# Connector_0_V1_01.net
KiCad netlist of a schematic drawn in Altium Designer
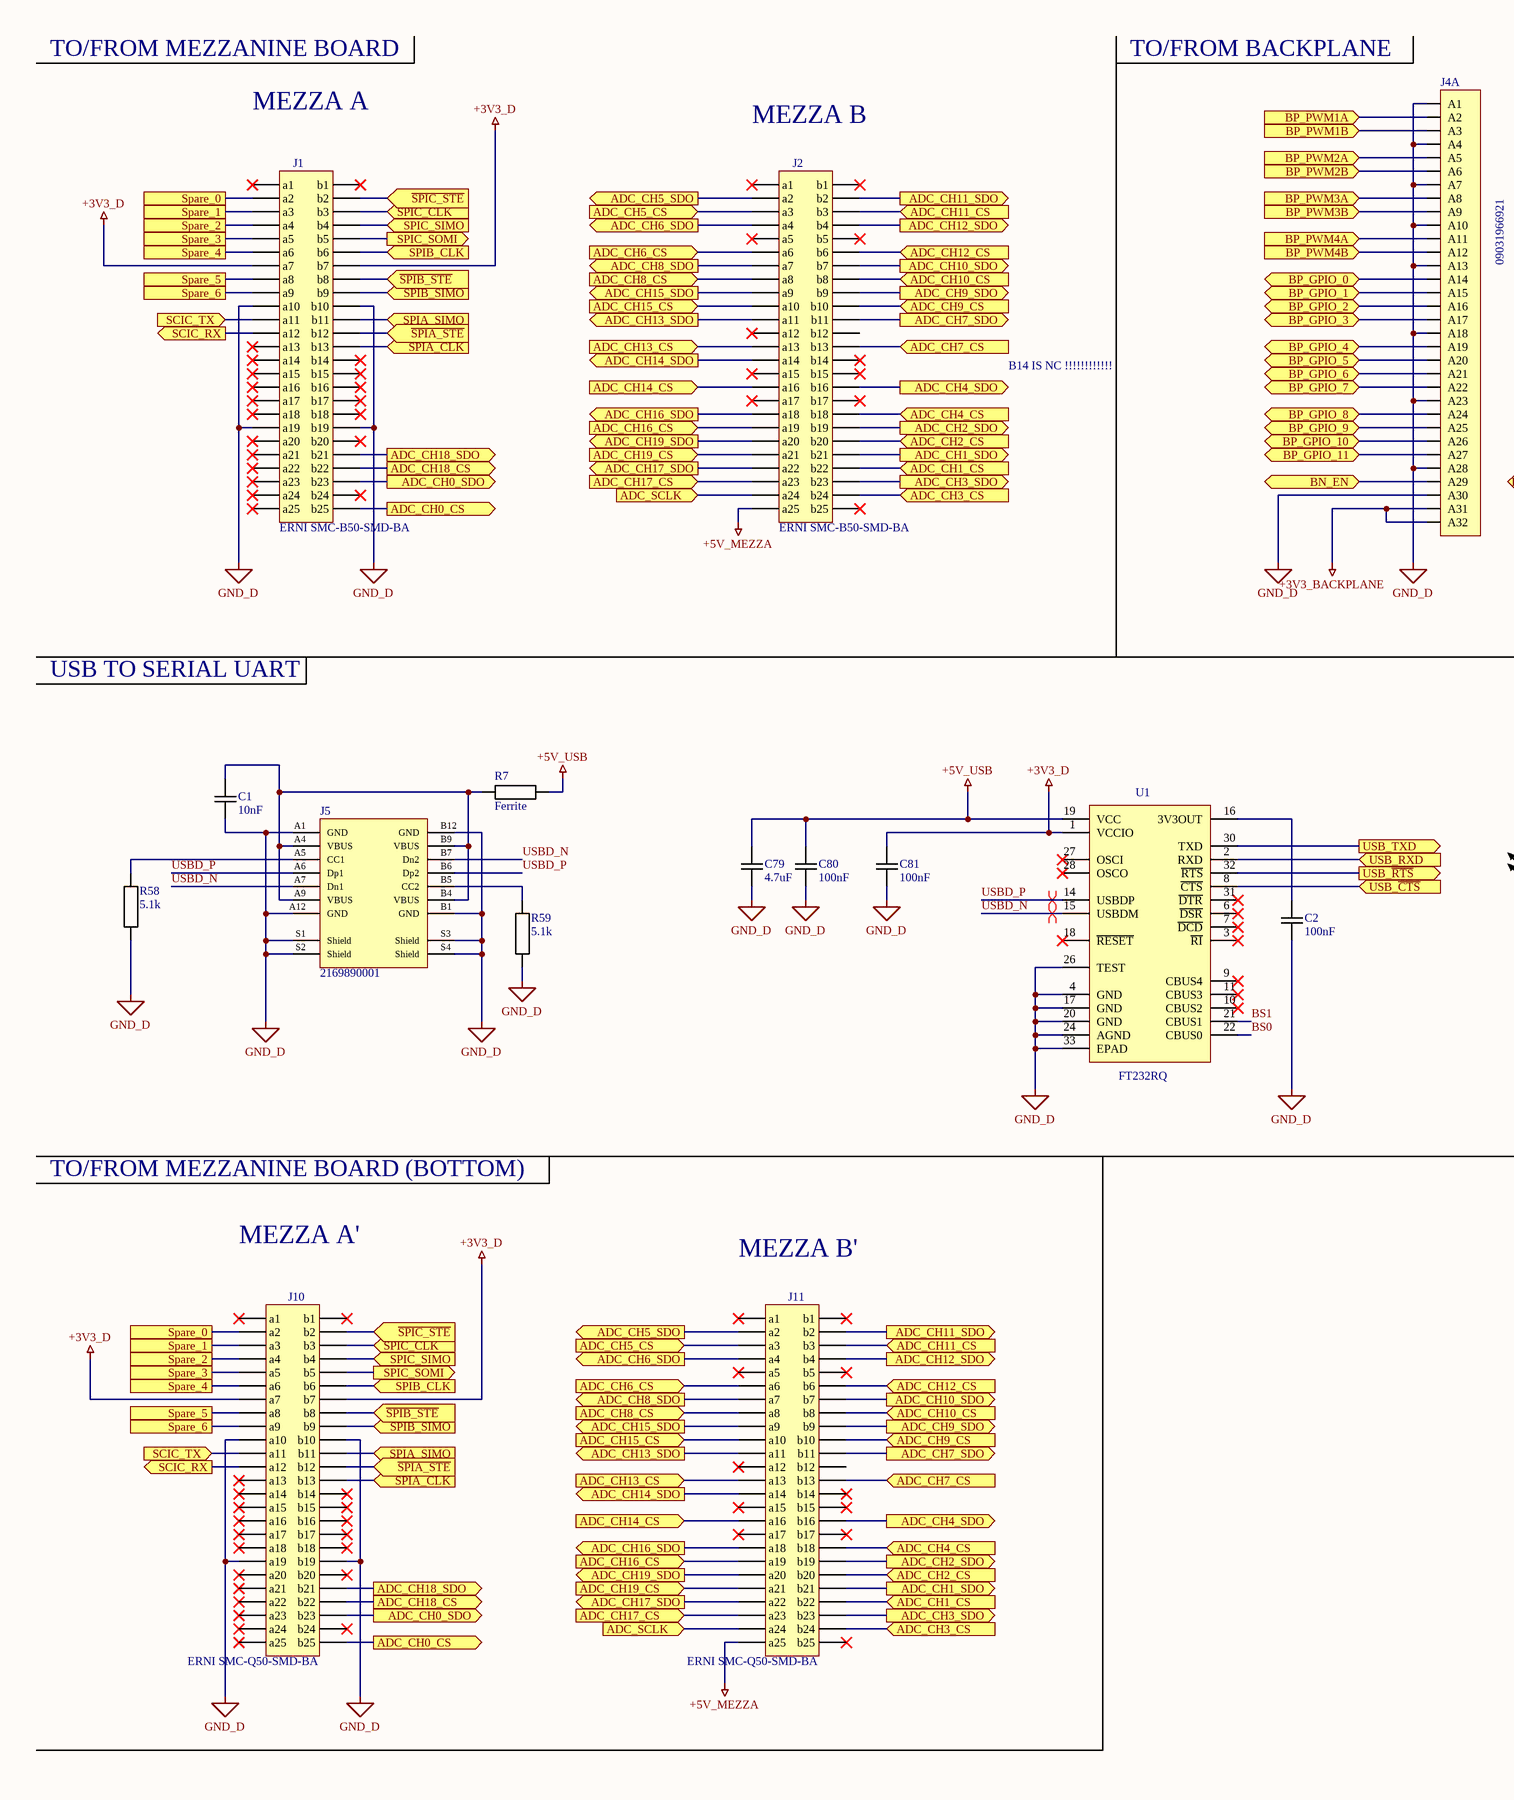
[diagram p0: Connector_0_V1_01.SchDoc, left]
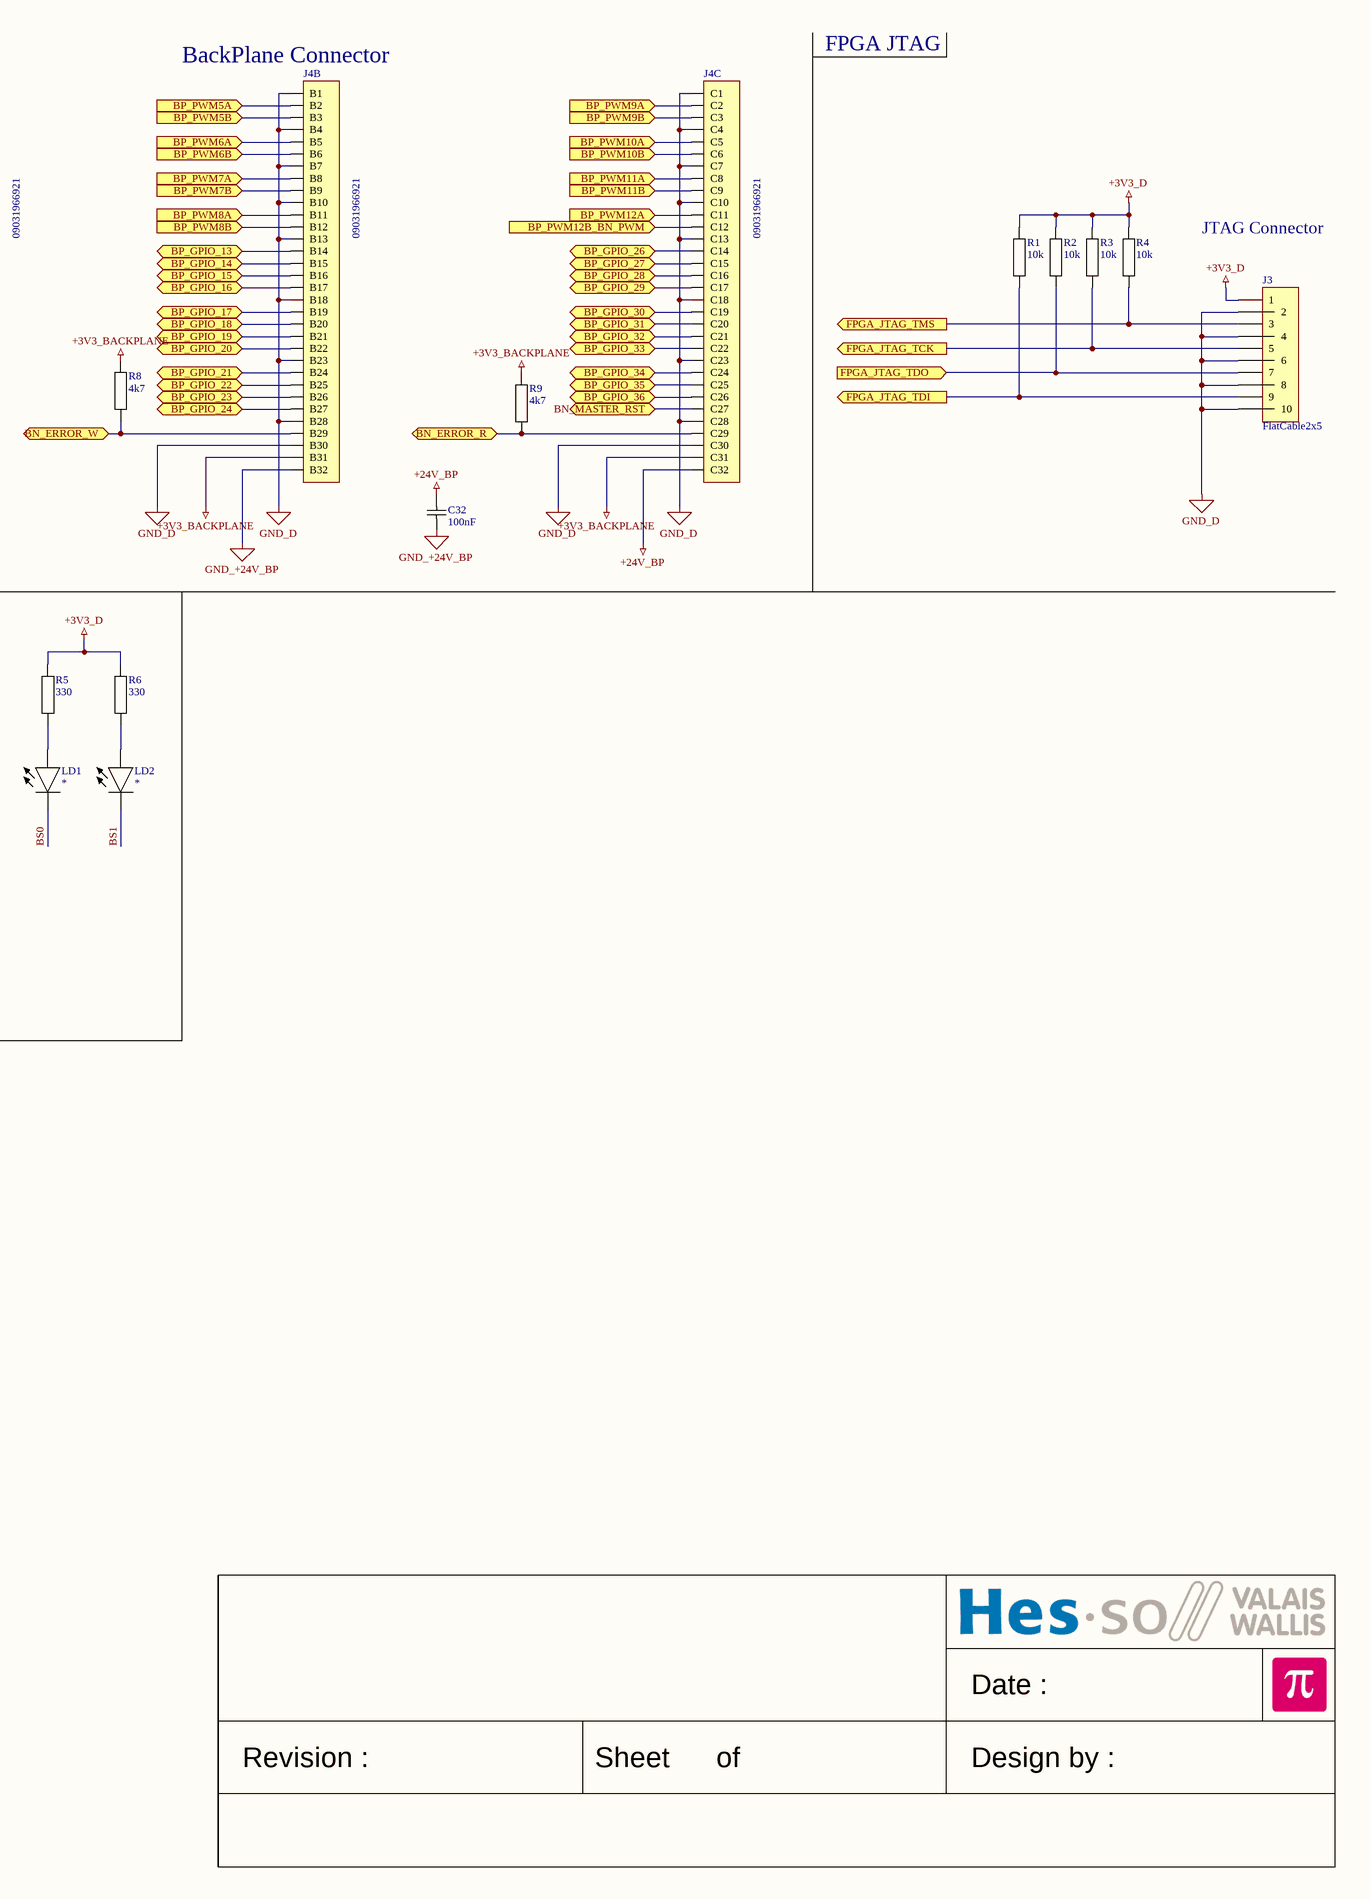
[diagram p1: Connector_0_V1_01.SchDoc, right]

(export (version "E")
  (design (tool "Eeschema 10.0.6"))
  (components
    (comp (ref "C1")
      (value "10nF")
      (footprint "CAPACITOR 1608 REFLOW")
      (description "Capacitor X7R 10% 50V 1608(0603)")
      (libsource (lib "Capacitor") (part "Capacitor"))
    )
    (comp (ref "C2")
      (value "100nF")
      (footprint "CAPACITOR 1608 REFLOW")
      (description "Capacitor X7R 10% 50V 1608(0603)")
      (libsource (lib "Capacitor") (part "Capacitor"))
    )
    (comp (ref "C32")
      (value "100nF")
      (footprint "CAPACITOR 1608 REFLOW")
      (description "Capacitor X7R 10% 50V 1608(0603)")
      (libsource (lib "Capacitor") (part "Capacitor"))
    )
    (comp (ref "C79")
      (value "4.7uF")
      (footprint "CAPACITOR 1608 REFLOW")
      (description "Capacitor X7R 10% 50V 1608(0603)")
      (libsource (lib "Capacitor") (part "Capacitor"))
    )
    (comp (ref "C80")
      (value "100nF")
      (footprint "CAPACITOR 1608 REFLOW")
      (description "Capacitor X7R 10% 50V 1608(0603)")
      (libsource (lib "Capacitor") (part "Capacitor"))
    )
    (comp (ref "C81")
      (value "100nF")
      (footprint "CAPACITOR 1608 REFLOW")
      (description "Capacitor X7R 10% 50V 1608(0603)")
      (libsource (lib "Capacitor") (part "Capacitor"))
    )
    (comp (ref "J1")
      (value "ERNI SMC-B50-SMD-BA")
      (footprint "ERNI SMC-B50-SMD-BA")
      (description "Female 1.27 pitch 2x25 pin connector")
      (libsource (lib "Connector") (part "ERNI SMC-B50-SMD-BA"))
    )
    (comp (ref "J2")
      (value "ERNI SMC-B50-SMD-BA")
      (footprint "ERNI SMC-B50-SMD-BA")
      (description "Female 1.27 pitch 2x25 pin connector")
      (libsource (lib "Connector") (part "ERNI SMC-B50-SMD-BA"))
    )
    (comp (ref "J3")
      (value "FlatCable2x5")
      (footprint "FlatCable2x5 2MM Right Angle TH FCI 98614-G61-10ULF")
      (libsource (lib "Connector") (part "FlatCable2x5"))
    )
    (comp (ref "J4")
      (value "09031966921")
      (footprint "DIN41612 MALE 3X32 ABC R90")
      (description "DIN41612 MALE 3X32 ABC R90")
      (fields (field (name "MANUFACTURER") "Harting"))
      (libsource (lib "Connector") (part "DIN41612 MALE 3X32 ABC R90"))
    )
    (comp (ref "J5")
      (value "2169890001")
      (footprint "USB-C-TH MOLEX 2169890001")
      (description "USB-C Receptacle Connector 24 Position Through Hole, Right Angle")
      (libsource (lib "Connector") (part "USB-C-Molex 2169890001"))
    )
    (comp (ref "J10")
      (value "ERNI SMC-Q50-SMD-BA")
      (footprint "ERNI SMC-Q50-SMD-BA")
      (description "Male 1.27 pitch 2x25 pin connector")
      (libsource (lib "Connector") (part "ERNI SMC-Q50-SMD-BA"))
    )
    (comp (ref "J11")
      (value "ERNI SMC-Q50-SMD-BA")
      (footprint "ERNI SMC-Q50-SMD-BA")
      (description "Male 1.27 pitch 2x25 pin connector")
      (libsource (lib "Connector") (part "ERNI SMC-Q50-SMD-BA"))
    )
    (comp (ref "LD1")
      (value "*")
      (footprint "LED 1608 REFLOW")
      (description "LED generic")
      (libsource (lib "Diode") (part "LED"))
    )
    (comp (ref "LD2")
      (value "*")
      (footprint "LED 1608 REFLOW")
      (description "LED generic")
      (libsource (lib "Diode") (part "LED"))
    )
    (comp (ref "R1")
      (value "10k")
      (footprint "RESISTOR 1608 REFLOW")
      (description "Resistor 1% 50V 100mW 1608(0603)")
      (libsource (lib "Resistor") (part "Resistor"))
    )
    (comp (ref "R2")
      (value "10k")
      (footprint "RESISTOR 1608 REFLOW")
      (description "Resistor 1% 50V 100mW 1608(0603)")
      (libsource (lib "Resistor") (part "Resistor"))
    )
    (comp (ref "R3")
      (value "10k")
      (footprint "RESISTOR 1608 REFLOW")
      (description "Resistor 1% 50V 100mW 1608(0603)")
      (libsource (lib "Resistor") (part "Resistor"))
    )
    (comp (ref "R4")
      (value "10k")
      (footprint "RESISTOR 1608 REFLOW")
      (description "Resistor 1% 50V 100mW 1608(0603)")
      (libsource (lib "Resistor") (part "Resistor"))
    )
    (comp (ref "R5")
      (value "330")
      (footprint "RESISTOR 1608 REFLOW")
      (description "Resistor 1% 50V 125mW 2012(0805)")
      (libsource (lib "Resistor") (part "Resistor"))
    )
    (comp (ref "R6")
      (value "330")
      (footprint "RESISTOR 1608 REFLOW")
      (description "Resistor 1% 50V 125mW 2012(0805)")
      (libsource (lib "Resistor") (part "Resistor"))
    )
    (comp (ref "R7")
      (value "Ferrite")
      (footprint "RESISTOR 1608 REFLOW")
      (description "Resistor 1% 50V 100mW 1608(0603)")
      (libsource (lib "Resistor") (part "Resistor"))
    )
    (comp (ref "R8")
      (value "4k7")
      (footprint "RESISTOR 1608 REFLOW")
      (description "Resistor 1% 50V 100mW 1608(0603)")
      (libsource (lib "Resistor") (part "Resistor"))
    )
    (comp (ref "R9")
      (value "4k7")
      (footprint "RESISTOR 1608 REFLOW")
      (description "Resistor 1% 50V 100mW 1608(0603)")
      (libsource (lib "Resistor") (part "Resistor"))
    )
    (comp (ref "R58")
      (value "5.1k")
      (footprint "RESISTOR 1608 REFLOW")
      (description "Resistor 1% 50V 100mW 1608(0603)")
      (libsource (lib "Resistor") (part "Resistor"))
    )
    (comp (ref "R59")
      (value "5.1k")
      (footprint "RESISTOR 1608 REFLOW")
      (description "Resistor 1% 50V 100mW 1608(0603)")
      (libsource (lib "Resistor") (part "Resistor"))
    )
    (comp (ref "U1")
      (value "FT232RQ")
      (footprint "QFN32 P0.5 T3.2x3.2 C5.0X5.0 H1.0")
      (description "24-Bit ADC with Ultra Low Noise PGIA - Crystal")
      (libsource (lib "IntegratedCircuit - Copy") (part "FT232RQ"))
    )
  )
  (nets
    (net (code "1") (name "+3V3_BACKPLANE") (class "Default")
      (node (ref "J4") (pin "A31") (pinfunction "A31_A31") (pintype "passive"))
      (node (ref "J4") (pin "A32") (pinfunction "A32_A32") (pintype "passive"))
      (node (ref "J4") (pin "B31") (pinfunction "B31_B31") (pintype "passive"))
      (node (ref "J4") (pin "C31") (pinfunction "C31_C31") (pintype "passive"))
      (node (ref "R8") (pin "2") (pinfunction "2_2") (pintype "passive"))
      (node (ref "R9") (pin "2") (pinfunction "2_2") (pintype "passive"))
    )
    (net (code "2") (name "+3V3_D") (class "Default")
      (node (ref "C81") (pin "2") (pinfunction "2_2") (pintype "passive"))
      (node (ref "J1") (pin "a7") (pinfunction "a7_a7") (pintype "passive"))
      (node (ref "J1") (pin "b7") (pinfunction "b7_b7") (pintype "passive"))
      (node (ref "J10") (pin "a7") (pinfunction "a7_a7") (pintype "passive"))
      (node (ref "J10") (pin "b7") (pinfunction "b7_b7") (pintype "passive"))
      (node (ref "J3") (pin "1") (pinfunction "1_1") (pintype "passive"))
      (node (ref "R1") (pin "2") (pinfunction "2_2") (pintype "passive"))
      (node (ref "R2") (pin "2") (pinfunction "2_2") (pintype "passive"))
      (node (ref "R3") (pin "2") (pinfunction "2_2") (pintype "passive"))
      (node (ref "R4") (pin "2") (pinfunction "2_2") (pintype "passive"))
      (node (ref "R5") (pin "2") (pinfunction "2_2") (pintype "passive"))
      (node (ref "R6") (pin "2") (pinfunction "2_2") (pintype "passive"))
      (node (ref "U1") (pin "1") (pinfunction "VCCIO_1") (pintype "passive"))
    )
    (net (code "3") (name "+5V_MEZZA") (class "Default")
      (node (ref "J11") (pin "a25") (pinfunction "a25_a25") (pintype "passive"))
      (node (ref "J2") (pin "a25") (pinfunction "a25_a25") (pintype "passive"))
    )
    (net (code "4") (name "+5V_USB") (class "Default")
      (node (ref "C79") (pin "2") (pinfunction "2_2") (pintype "passive"))
      (node (ref "C80") (pin "2") (pinfunction "2_2") (pintype "passive"))
      (node (ref "R7") (pin "2") (pinfunction "2_2") (pintype "passive"))
      (node (ref "U1") (pin "19") (pinfunction "VCC_19") (pintype "passive"))
    )
    (net (code "5") (name "+24V_BP") (class "Default")
      (node (ref "C32") (pin "2") (pinfunction "2_2") (pintype "passive"))
      (node (ref "J4") (pin "C32") (pinfunction "C32_C32") (pintype "passive"))
    )
    (net (code "6") (name "/ADC_CH0_CS") (class "Default")
      (node (ref "J1") (pin "b25") (pinfunction "b25_b25") (pintype "passive"))
      (node (ref "J10") (pin "b25") (pinfunction "b25_b25") (pintype "passive"))
    )
    (net (code "7") (name "/ADC_CH0_SDO") (class "Default")
      (node (ref "J1") (pin "b23") (pinfunction "b23_b23") (pintype "passive"))
      (node (ref "J10") (pin "b23") (pinfunction "b23_b23") (pintype "passive"))
    )
    (net (code "8") (name "/ADC_CH1_CS") (class "Default")
      (node (ref "J11") (pin "b22") (pinfunction "b22_b22") (pintype "passive"))
      (node (ref "J2") (pin "b22") (pinfunction "b22_b22") (pintype "passive"))
    )
    (net (code "9") (name "/ADC_CH1_SDO") (class "Default")
      (node (ref "J11") (pin "b21") (pinfunction "b21_b21") (pintype "passive"))
      (node (ref "J2") (pin "b21") (pinfunction "b21_b21") (pintype "passive"))
    )
    (net (code "10") (name "/ADC_CH2_CS") (class "Default")
      (node (ref "J11") (pin "b20") (pinfunction "b20_b20") (pintype "passive"))
      (node (ref "J2") (pin "b20") (pinfunction "b20_b20") (pintype "passive"))
    )
    (net (code "11") (name "/ADC_CH2_SDO") (class "Default")
      (node (ref "J11") (pin "b19") (pinfunction "b19_b19") (pintype "passive"))
      (node (ref "J2") (pin "b19") (pinfunction "b19_b19") (pintype "passive"))
    )
    (net (code "12") (name "/ADC_CH3_CS") (class "Default")
      (node (ref "J11") (pin "b24") (pinfunction "b24_b24") (pintype "passive"))
      (node (ref "J2") (pin "b24") (pinfunction "b24_b24") (pintype "passive"))
    )
    (net (code "13") (name "/ADC_CH3_SDO") (class "Default")
      (node (ref "J11") (pin "b23") (pinfunction "b23_b23") (pintype "passive"))
      (node (ref "J2") (pin "b23") (pinfunction "b23_b23") (pintype "passive"))
    )
    (net (code "14") (name "/ADC_CH4_CS") (class "Default")
      (node (ref "J11") (pin "b18") (pinfunction "b18_b18") (pintype "passive"))
      (node (ref "J2") (pin "b18") (pinfunction "b18_b18") (pintype "passive"))
    )
    (net (code "15") (name "/ADC_CH4_SDO") (class "Default")
      (node (ref "J11") (pin "b16") (pinfunction "b16_b16") (pintype "passive"))
      (node (ref "J2") (pin "b16") (pinfunction "b16_b16") (pintype "passive"))
    )
    (net (code "16") (name "/ADC_CH5_CS") (class "Default")
      (node (ref "J11") (pin "a3") (pinfunction "a3_a3") (pintype "passive"))
      (node (ref "J2") (pin "a3") (pinfunction "a3_a3") (pintype "passive"))
    )
    (net (code "17") (name "/ADC_CH5_SDO") (class "Default")
      (node (ref "J11") (pin "a2") (pinfunction "a2_a2") (pintype "passive"))
      (node (ref "J2") (pin "a2") (pinfunction "a2_a2") (pintype "passive"))
    )
    (net (code "18") (name "/ADC_CH6_CS") (class "Default")
      (node (ref "J11") (pin "a6") (pinfunction "a6_a6") (pintype "passive"))
      (node (ref "J2") (pin "a6") (pinfunction "a6_a6") (pintype "passive"))
    )
    (net (code "19") (name "/ADC_CH6_SDO") (class "Default")
      (node (ref "J11") (pin "a4") (pinfunction "a4_a4") (pintype "passive"))
      (node (ref "J2") (pin "a4") (pinfunction "a4_a4") (pintype "passive"))
    )
    (net (code "20") (name "/ADC_CH7_CS") (class "Default")
      (node (ref "J11") (pin "b13") (pinfunction "b13_b13") (pintype "passive"))
      (node (ref "J2") (pin "b13") (pinfunction "b13_b13") (pintype "passive"))
    )
    (net (code "21") (name "/ADC_CH7_SDO") (class "Default")
      (node (ref "J11") (pin "b11") (pinfunction "b11_b11") (pintype "passive"))
      (node (ref "J2") (pin "b11") (pinfunction "b11_b11") (pintype "passive"))
    )
    (net (code "22") (name "/ADC_CH8_CS") (class "Default")
      (node (ref "J11") (pin "a8") (pinfunction "a8_a8") (pintype "passive"))
      (node (ref "J2") (pin "a8") (pinfunction "a8_a8") (pintype "passive"))
    )
    (net (code "23") (name "/ADC_CH8_SDO") (class "Default")
      (node (ref "J11") (pin "a7") (pinfunction "a7_a7") (pintype "passive"))
      (node (ref "J2") (pin "a7") (pinfunction "a7_a7") (pintype "passive"))
    )
    (net (code "24") (name "/ADC_CH9_CS") (class "Default")
      (node (ref "J11") (pin "b10") (pinfunction "b10_b10") (pintype "passive"))
      (node (ref "J2") (pin "b10") (pinfunction "b10_b10") (pintype "passive"))
    )
    (net (code "25") (name "/ADC_CH9_SDO") (class "Default")
      (node (ref "J11") (pin "b9") (pinfunction "b9_b9") (pintype "passive"))
      (node (ref "J2") (pin "b9") (pinfunction "b9_b9") (pintype "passive"))
    )
    (net (code "26") (name "/ADC_CH10_CS") (class "Default")
      (node (ref "J11") (pin "b8") (pinfunction "b8_b8") (pintype "passive"))
      (node (ref "J2") (pin "b8") (pinfunction "b8_b8") (pintype "passive"))
    )
    (net (code "27") (name "/ADC_CH10_SDO") (class "Default")
      (node (ref "J11") (pin "b7") (pinfunction "b7_b7") (pintype "passive"))
      (node (ref "J2") (pin "b7") (pinfunction "b7_b7") (pintype "passive"))
    )
    (net (code "28") (name "/ADC_CH11_CS") (class "Default")
      (node (ref "J11") (pin "b3") (pinfunction "b3_b3") (pintype "passive"))
      (node (ref "J2") (pin "b3") (pinfunction "b3_b3") (pintype "passive"))
    )
    (net (code "29") (name "/ADC_CH11_SDO") (class "Default")
      (node (ref "J11") (pin "b2") (pinfunction "b2_b2") (pintype "passive"))
      (node (ref "J2") (pin "b2") (pinfunction "b2_b2") (pintype "passive"))
    )
    (net (code "30") (name "/ADC_CH12_CS") (class "Default")
      (node (ref "J11") (pin "b6") (pinfunction "b6_b6") (pintype "passive"))
      (node (ref "J2") (pin "b6") (pinfunction "b6_b6") (pintype "passive"))
    )
    (net (code "31") (name "/ADC_CH12_SDO") (class "Default")
      (node (ref "J11") (pin "b4") (pinfunction "b4_b4") (pintype "passive"))
      (node (ref "J2") (pin "b4") (pinfunction "b4_b4") (pintype "passive"))
    )
    (net (code "32") (name "/ADC_CH13_CS") (class "Default")
      (node (ref "J11") (pin "a13") (pinfunction "a13_a13") (pintype "passive"))
      (node (ref "J2") (pin "a13") (pinfunction "a13_a13") (pintype "passive"))
    )
    (net (code "33") (name "/ADC_CH13_SDO") (class "Default")
      (node (ref "J11") (pin "a11") (pinfunction "a11_a11") (pintype "passive"))
      (node (ref "J2") (pin "a11") (pinfunction "a11_a11") (pintype "passive"))
    )
    (net (code "34") (name "/ADC_CH14_CS") (class "Default")
      (node (ref "J11") (pin "a16") (pinfunction "a16_a16") (pintype "passive"))
      (node (ref "J2") (pin "a16") (pinfunction "a16_a16") (pintype "passive"))
    )
    (net (code "35") (name "/ADC_CH14_SDO") (class "Default")
      (node (ref "J11") (pin "a14") (pinfunction "a14_a14") (pintype "passive"))
      (node (ref "J2") (pin "a14") (pinfunction "a14_a14") (pintype "passive"))
    )
    (net (code "36") (name "/ADC_CH15_CS") (class "Default")
      (node (ref "J11") (pin "a10") (pinfunction "a10_a10") (pintype "passive"))
      (node (ref "J2") (pin "a10") (pinfunction "a10_a10") (pintype "passive"))
    )
    (net (code "37") (name "/ADC_CH15_SDO") (class "Default")
      (node (ref "J11") (pin "a9") (pinfunction "a9_a9") (pintype "passive"))
      (node (ref "J2") (pin "a9") (pinfunction "a9_a9") (pintype "passive"))
    )
    (net (code "38") (name "/ADC_CH16_CS") (class "Default")
      (node (ref "J11") (pin "a19") (pinfunction "a19_a19") (pintype "passive"))
      (node (ref "J2") (pin "a19") (pinfunction "a19_a19") (pintype "passive"))
    )
    (net (code "39") (name "/ADC_CH16_SDO") (class "Default")
      (node (ref "J11") (pin "a18") (pinfunction "a18_a18") (pintype "passive"))
      (node (ref "J2") (pin "a18") (pinfunction "a18_a18") (pintype "passive"))
    )
    (net (code "40") (name "/ADC_CH17_CS") (class "Default")
      (node (ref "J11") (pin "a23") (pinfunction "a23_a23") (pintype "passive"))
      (node (ref "J2") (pin "a23") (pinfunction "a23_a23") (pintype "passive"))
    )
    (net (code "41") (name "/ADC_CH17_SDO") (class "Default")
      (node (ref "J11") (pin "a22") (pinfunction "a22_a22") (pintype "passive"))
      (node (ref "J2") (pin "a22") (pinfunction "a22_a22") (pintype "passive"))
    )
    (net (code "42") (name "/ADC_CH18_CS") (class "Default")
      (node (ref "J1") (pin "b22") (pinfunction "b22_b22") (pintype "passive"))
      (node (ref "J10") (pin "b22") (pinfunction "b22_b22") (pintype "passive"))
    )
    (net (code "43") (name "/ADC_CH18_SDO") (class "Default")
      (node (ref "J1") (pin "b21") (pinfunction "b21_b21") (pintype "passive"))
      (node (ref "J10") (pin "b21") (pinfunction "b21_b21") (pintype "passive"))
    )
    (net (code "44") (name "/ADC_CH19_CS") (class "Default")
      (node (ref "J11") (pin "a21") (pinfunction "a21_a21") (pintype "passive"))
      (node (ref "J2") (pin "a21") (pinfunction "a21_a21") (pintype "passive"))
    )
    (net (code "45") (name "/ADC_CH19_SDO") (class "Default")
      (node (ref "J11") (pin "a20") (pinfunction "a20_a20") (pintype "passive"))
      (node (ref "J2") (pin "a20") (pinfunction "a20_a20") (pintype "passive"))
    )
    (net (code "46") (name "/ADC_SCLK") (class "Default")
      (node (ref "J11") (pin "a24") (pinfunction "a24_a24") (pintype "passive"))
      (node (ref "J2") (pin "a24") (pinfunction "a24_a24") (pintype "passive"))
    )
    (net (code "47") (name "/BN_EN") (class "Default")
      (node (ref "J4") (pin "A29") (pinfunction "A29_A29") (pintype "passive"))
    )
    (net (code "48") (name "/BN_ERROR_R") (class "Default")
      (node (ref "J4") (pin "C29") (pinfunction "C29_C29") (pintype "passive"))
      (node (ref "R9") (pin "1") (pinfunction "1_1") (pintype "passive"))
    )
    (net (code "49") (name "/BN_ERROR_W") (class "Default")
      (node (ref "J4") (pin "B29") (pinfunction "B29_B29") (pintype "passive"))
      (node (ref "R8") (pin "1") (pinfunction "1_1") (pintype "passive"))
    )
    (net (code "50") (name "/BN_MASTER_RST") (class "Default")
      (node (ref "J4") (pin "C27") (pinfunction "C27_C27") (pintype "passive"))
    )
    (net (code "51") (name "/BP_GPIO_0") (class "Default")
      (node (ref "J4") (pin "A14") (pinfunction "A14_A14") (pintype "passive"))
    )
    (net (code "52") (name "/BP_GPIO_1") (class "Default")
      (node (ref "J4") (pin "A15") (pinfunction "A15_A15") (pintype "passive"))
    )
    (net (code "53") (name "/BP_GPIO_2") (class "Default")
      (node (ref "J4") (pin "A16") (pinfunction "A16_A16") (pintype "passive"))
    )
    (net (code "54") (name "/BP_GPIO_3") (class "Default")
      (node (ref "J4") (pin "A17") (pinfunction "A17_A17") (pintype "passive"))
    )
    (net (code "55") (name "/BP_GPIO_4") (class "Default")
      (node (ref "J4") (pin "A19") (pinfunction "A19_A19") (pintype "passive"))
    )
    (net (code "56") (name "/BP_GPIO_5") (class "Default")
      (node (ref "J4") (pin "A20") (pinfunction "A20_A20") (pintype "passive"))
    )
    (net (code "57") (name "/BP_GPIO_6") (class "Default")
      (node (ref "J4") (pin "A21") (pinfunction "A21_A21") (pintype "passive"))
    )
    (net (code "58") (name "/BP_GPIO_7") (class "Default")
      (node (ref "J4") (pin "A22") (pinfunction "A22_A22") (pintype "passive"))
    )
    (net (code "59") (name "/BP_GPIO_8") (class "Default")
      (node (ref "J4") (pin "A24") (pinfunction "A24_A24") (pintype "passive"))
    )
    (net (code "60") (name "/BP_GPIO_9") (class "Default")
      (node (ref "J4") (pin "A25") (pinfunction "A25_A25") (pintype "passive"))
    )
    (net (code "61") (name "/BP_GPIO_10") (class "Default")
      (node (ref "J4") (pin "A26") (pinfunction "A26_A26") (pintype "passive"))
    )
    (net (code "62") (name "/BP_GPIO_11") (class "Default")
      (node (ref "J4") (pin "A27") (pinfunction "A27_A27") (pintype "passive"))
    )
    (net (code "63") (name "/BP_GPIO_13") (class "Default")
      (node (ref "J4") (pin "B14") (pinfunction "B14_B14") (pintype "passive"))
    )
    (net (code "64") (name "/BP_GPIO_14") (class "Default")
      (node (ref "J4") (pin "B15") (pinfunction "B15_B15") (pintype "passive"))
    )
    (net (code "65") (name "/BP_GPIO_15") (class "Default")
      (node (ref "J4") (pin "B16") (pinfunction "B16_B16") (pintype "passive"))
    )
    (net (code "66") (name "/BP_GPIO_16") (class "Default")
      (node (ref "J4") (pin "B17") (pinfunction "B17_B17") (pintype "passive"))
    )
    (net (code "67") (name "/BP_GPIO_17") (class "Default")
      (node (ref "J4") (pin "B19") (pinfunction "B19_B19") (pintype "passive"))
    )
    (net (code "68") (name "/BP_GPIO_18") (class "Default")
      (node (ref "J4") (pin "B20") (pinfunction "B20_B20") (pintype "passive"))
    )
    (net (code "69") (name "/BP_GPIO_19") (class "Default")
      (node (ref "J4") (pin "B21") (pinfunction "B21_B21") (pintype "passive"))
    )
    (net (code "70") (name "/BP_GPIO_20") (class "Default")
      (node (ref "J4") (pin "B22") (pinfunction "B22_B22") (pintype "passive"))
    )
    (net (code "71") (name "/BP_GPIO_21") (class "Default")
      (node (ref "J4") (pin "B24") (pinfunction "B24_B24") (pintype "passive"))
    )
    (net (code "72") (name "/BP_GPIO_22") (class "Default")
      (node (ref "J4") (pin "B25") (pinfunction "B25_B25") (pintype "passive"))
    )
    (net (code "73") (name "/BP_GPIO_23") (class "Default")
      (node (ref "J4") (pin "B26") (pinfunction "B26_B26") (pintype "passive"))
    )
    (net (code "74") (name "/BP_GPIO_24") (class "Default")
      (node (ref "J4") (pin "B27") (pinfunction "B27_B27") (pintype "passive"))
    )
    (net (code "75") (name "/BP_GPIO_26") (class "Default")
      (node (ref "J4") (pin "C14") (pinfunction "C14_C14") (pintype "passive"))
    )
    (net (code "76") (name "/BP_GPIO_27") (class "Default")
      (node (ref "J4") (pin "C15") (pinfunction "C15_C15") (pintype "passive"))
    )
    (net (code "77") (name "/BP_GPIO_28") (class "Default")
      (node (ref "J4") (pin "C16") (pinfunction "C16_C16") (pintype "passive"))
    )
    (net (code "78") (name "/BP_GPIO_29") (class "Default")
      (node (ref "J4") (pin "C17") (pinfunction "C17_C17") (pintype "passive"))
    )
    (net (code "79") (name "/BP_GPIO_30") (class "Default")
      (node (ref "J4") (pin "C19") (pinfunction "C19_C19") (pintype "passive"))
    )
    (net (code "80") (name "/BP_GPIO_31") (class "Default")
      (node (ref "J4") (pin "C20") (pinfunction "C20_C20") (pintype "passive"))
    )
    (net (code "81") (name "/BP_GPIO_32") (class "Default")
      (node (ref "J4") (pin "C21") (pinfunction "C21_C21") (pintype "passive"))
    )
    (net (code "82") (name "/BP_GPIO_33") (class "Default")
      (node (ref "J4") (pin "C22") (pinfunction "C22_C22") (pintype "passive"))
    )
    (net (code "83") (name "/BP_GPIO_34") (class "Default")
      (node (ref "J4") (pin "C24") (pinfunction "C24_C24") (pintype "passive"))
    )
    (net (code "84") (name "/BP_GPIO_35") (class "Default")
      (node (ref "J4") (pin "C25") (pinfunction "C25_C25") (pintype "passive"))
    )
    (net (code "85") (name "/BP_GPIO_36") (class "Default")
      (node (ref "J4") (pin "C26") (pinfunction "C26_C26") (pintype "passive"))
    )
    (net (code "86") (name "/BP_PWM1A") (class "Default")
      (node (ref "J4") (pin "A2") (pinfunction "A2_A2") (pintype "passive"))
    )
    (net (code "87") (name "/BP_PWM1B") (class "Default")
      (node (ref "J4") (pin "A3") (pinfunction "A3_A3") (pintype "passive"))
    )
    (net (code "88") (name "/BP_PWM2A") (class "Default")
      (node (ref "J4") (pin "A5") (pinfunction "A5_A5") (pintype "passive"))
    )
    (net (code "89") (name "/BP_PWM2B") (class "Default")
      (node (ref "J4") (pin "A6") (pinfunction "A6_A6") (pintype "passive"))
    )
    (net (code "90") (name "/BP_PWM3A") (class "Default")
      (node (ref "J4") (pin "A8") (pinfunction "A8_A8") (pintype "passive"))
    )
    (net (code "91") (name "/BP_PWM3B") (class "Default")
      (node (ref "J4") (pin "A9") (pinfunction "A9_A9") (pintype "passive"))
    )
    (net (code "92") (name "/BP_PWM4A") (class "Default")
      (node (ref "J4") (pin "A11") (pinfunction "A11_A11") (pintype "passive"))
    )
    (net (code "93") (name "/BP_PWM4B") (class "Default")
      (node (ref "J4") (pin "A12") (pinfunction "A12_A12") (pintype "passive"))
    )
    (net (code "94") (name "/BP_PWM5A") (class "Default")
      (node (ref "J4") (pin "B2") (pinfunction "B2_B2") (pintype "passive"))
    )
    (net (code "95") (name "/BP_PWM5B") (class "Default")
      (node (ref "J4") (pin "B3") (pinfunction "B3_B3") (pintype "passive"))
    )
    (net (code "96") (name "/BP_PWM6A") (class "Default")
      (node (ref "J4") (pin "B5") (pinfunction "B5_B5") (pintype "passive"))
    )
    (net (code "97") (name "/BP_PWM6B") (class "Default")
      (node (ref "J4") (pin "B6") (pinfunction "B6_B6") (pintype "passive"))
    )
    (net (code "98") (name "/BP_PWM7A") (class "Default")
      (node (ref "J4") (pin "B8") (pinfunction "B8_B8") (pintype "passive"))
    )
    (net (code "99") (name "/BP_PWM7B") (class "Default")
      (node (ref "J4") (pin "B9") (pinfunction "B9_B9") (pintype "passive"))
    )
    (net (code "100") (name "/BP_PWM8A") (class "Default")
      (node (ref "J4") (pin "B11") (pinfunction "B11_B11") (pintype "passive"))
    )
    (net (code "101") (name "/BP_PWM8B") (class "Default")
      (node (ref "J4") (pin "B12") (pinfunction "B12_B12") (pintype "passive"))
    )
    (net (code "102") (name "/BP_PWM9A") (class "Default")
      (node (ref "J4") (pin "C2") (pinfunction "C2_C2") (pintype "passive"))
    )
    (net (code "103") (name "/BP_PWM9B") (class "Default")
      (node (ref "J4") (pin "C3") (pinfunction "C3_C3") (pintype "passive"))
    )
    (net (code "104") (name "/BP_PWM10A") (class "Default")
      (node (ref "J4") (pin "C5") (pinfunction "C5_C5") (pintype "passive"))
    )
    (net (code "105") (name "/BP_PWM10B") (class "Default")
      (node (ref "J4") (pin "C6") (pinfunction "C6_C6") (pintype "passive"))
    )
    (net (code "106") (name "/BP_PWM11A") (class "Default")
      (node (ref "J4") (pin "C8") (pinfunction "C8_C8") (pintype "passive"))
    )
    (net (code "107") (name "/BP_PWM11B") (class "Default")
      (node (ref "J4") (pin "C9") (pinfunction "C9_C9") (pintype "passive"))
    )
    (net (code "108") (name "/BP_PWM12A") (class "Default")
      (node (ref "J4") (pin "C11") (pinfunction "C11_C11") (pintype "passive"))
    )
    (net (code "109") (name "/BP_PWM12B_BN_PWM") (class "Default")
      (node (ref "J4") (pin "C12") (pinfunction "C12_C12") (pintype "passive"))
    )
    (net (code "110") (name "/BS0") (class "Default")
      (node (ref "LD1") (pin "1") (pinfunction "C_1") (pintype "passive"))
      (node (ref "U1") (pin "22") (pinfunction "CBUS0_22") (pintype "passive"))
    )
    (net (code "111") (name "/BS1") (class "Default")
      (node (ref "LD2") (pin "1") (pinfunction "C_1") (pintype "passive"))
      (node (ref "U1") (pin "21") (pinfunction "CBUS1_21") (pintype "passive"))
    )
    (net (code "112") (name "/FPGA_JTAG_TCK") (class "Default")
      (node (ref "J3") (pin "5") (pinfunction "5_5") (pintype "passive"))
      (node (ref "R3") (pin "1") (pinfunction "1_1") (pintype "passive"))
    )
    (net (code "113") (name "/FPGA_JTAG_TDI") (class "Default")
      (node (ref "J3") (pin "9") (pinfunction "9_9") (pintype "passive"))
      (node (ref "R1") (pin "1") (pinfunction "1_1") (pintype "passive"))
    )
    (net (code "114") (name "/FPGA_JTAG_TDO") (class "Default")
      (node (ref "J3") (pin "7") (pinfunction "7_7") (pintype "passive"))
      (node (ref "R2") (pin "1") (pinfunction "1_1") (pintype "passive"))
    )
    (net (code "115") (name "/FPGA_JTAG_TMS") (class "Default")
      (node (ref "J3") (pin "3") (pinfunction "3_3") (pintype "passive"))
      (node (ref "R4") (pin "1") (pinfunction "1_1") (pintype "passive"))
    )
    (net (code "116") (name "/SCIC_RX") (class "Default")
      (node (ref "J1") (pin "a12") (pinfunction "a12_a12") (pintype "passive"))
      (node (ref "J10") (pin "a12") (pinfunction "a12_a12") (pintype "passive"))
    )
    (net (code "117") (name "/SCIC_TX") (class "Default")
      (node (ref "J1") (pin "a11") (pinfunction "a11_a11") (pintype "passive"))
      (node (ref "J10") (pin "a11") (pinfunction "a11_a11") (pintype "passive"))
    )
    (net (code "118") (name "/SPIA_CLK") (class "Default")
      (node (ref "J1") (pin "b13") (pinfunction "b13_b13") (pintype "passive"))
      (node (ref "J10") (pin "b13") (pinfunction "b13_b13") (pintype "passive"))
    )
    (net (code "119") (name "/SPIA_SIMO") (class "Default")
      (node (ref "J1") (pin "b11") (pinfunction "b11_b11") (pintype "passive"))
      (node (ref "J10") (pin "b11") (pinfunction "b11_b11") (pintype "passive"))
    )
    (net (code "120") (name "/SPIB_CLK") (class "Default")
      (node (ref "J1") (pin "b6") (pinfunction "b6_b6") (pintype "passive"))
      (node (ref "J10") (pin "b6") (pinfunction "b6_b6") (pintype "passive"))
    )
    (net (code "121") (name "/SPIB_SIMO") (class "Default")
      (node (ref "J1") (pin "b9") (pinfunction "b9_b9") (pintype "passive"))
      (node (ref "J10") (pin "b9") (pinfunction "b9_b9") (pintype "passive"))
    )
    (net (code "122") (name "/SPIC_CLK") (class "Default")
      (node (ref "J1") (pin "b3") (pinfunction "b3_b3") (pintype "passive"))
      (node (ref "J10") (pin "b3") (pinfunction "b3_b3") (pintype "passive"))
    )
    (net (code "123") (name "/SPIC_SIMO") (class "Default")
      (node (ref "J1") (pin "b4") (pinfunction "b4_b4") (pintype "passive"))
      (node (ref "J10") (pin "b4") (pinfunction "b4_b4") (pintype "passive"))
    )
    (net (code "124") (name "/SPIC_SOMI") (class "Default")
      (node (ref "J1") (pin "b5") (pinfunction "b5_b5") (pintype "passive"))
      (node (ref "J10") (pin "b5") (pinfunction "b5_b5") (pintype "passive"))
    )
    (net (code "125") (name "/Spare_0") (class "Default")
      (node (ref "J1") (pin "a2") (pinfunction "a2_a2") (pintype "passive"))
      (node (ref "J10") (pin "a2") (pinfunction "a2_a2") (pintype "passive"))
    )
    (net (code "126") (name "/Spare_1") (class "Default")
      (node (ref "J1") (pin "a3") (pinfunction "a3_a3") (pintype "passive"))
      (node (ref "J10") (pin "a3") (pinfunction "a3_a3") (pintype "passive"))
    )
    (net (code "127") (name "/Spare_2") (class "Default")
      (node (ref "J1") (pin "a4") (pinfunction "a4_a4") (pintype "passive"))
      (node (ref "J10") (pin "a4") (pinfunction "a4_a4") (pintype "passive"))
    )
    (net (code "128") (name "/Spare_3") (class "Default")
      (node (ref "J1") (pin "a5") (pinfunction "a5_a5") (pintype "passive"))
      (node (ref "J10") (pin "a5") (pinfunction "a5_a5") (pintype "passive"))
    )
    (net (code "129") (name "/Spare_4") (class "Default")
      (node (ref "J1") (pin "a6") (pinfunction "a6_a6") (pintype "passive"))
      (node (ref "J10") (pin "a6") (pinfunction "a6_a6") (pintype "passive"))
    )
    (net (code "130") (name "/Spare_5") (class "Default")
      (node (ref "J1") (pin "a8") (pinfunction "a8_a8") (pintype "passive"))
      (node (ref "J10") (pin "a8") (pinfunction "a8_a8") (pintype "passive"))
    )
    (net (code "131") (name "/Spare_6") (class "Default")
      (node (ref "J1") (pin "a9") (pinfunction "a9_a9") (pintype "passive"))
      (node (ref "J10") (pin "a9") (pinfunction "a9_a9") (pintype "passive"))
    )
    (net (code "132") (name "/USBD_N") (class "Default")
      (node (ref "J5") (pin "A7") (pinfunction "Dn1_A7") (pintype "passive"))
      (node (ref "J5") (pin "B7") (pinfunction "Dn2_B7") (pintype "passive"))
      (node (ref "U1") (pin "15") (pinfunction "USBDM_15") (pintype "passive"))
    )
    (net (code "133") (name "/USBD_P") (class "Default")
      (node (ref "J5") (pin "A6") (pinfunction "Dp1_A6") (pintype "passive"))
      (node (ref "J5") (pin "B6") (pinfunction "Dp2_B6") (pintype "passive"))
      (node (ref "U1") (pin "14") (pinfunction "USBDP_14") (pintype "passive"))
    )
    (net (code "134") (name "/USB_RXD") (class "Default")
      (node (ref "U1") (pin "2") (pinfunction "RXD_2") (pintype "passive"))
    )
    (net (code "135") (name "/USB_TXD") (class "Default")
      (node (ref "U1") (pin "30") (pinfunction "TXD_30") (pintype "passive"))
    )
    (net (code "136") (name "/USB_~{CTS}") (class "Default")
      (node (ref "U1") (pin "8") (pinfunction "~{CTS}_8") (pintype "passive"))
    )
    (net (code "137") (name "/USB_~{RTS}") (class "Default")
      (node (ref "U1") (pin "32") (pinfunction "~{RTS}_32") (pintype "passive"))
    )
    (net (code "138") (name "/~{SPIA_STE}") (class "Default")
      (node (ref "J1") (pin "b12") (pinfunction "b12_b12") (pintype "passive"))
      (node (ref "J10") (pin "b12") (pinfunction "b12_b12") (pintype "passive"))
    )
    (net (code "139") (name "/~{SPIB_STE}") (class "Default")
      (node (ref "J1") (pin "b8") (pinfunction "b8_b8") (pintype "passive"))
      (node (ref "J10") (pin "b8") (pinfunction "b8_b8") (pintype "passive"))
    )
    (net (code "140") (name "/~{SPIC_STE}") (class "Default")
      (node (ref "J1") (pin "b2") (pinfunction "b2_b2") (pintype "passive"))
      (node (ref "J10") (pin "b2") (pinfunction "b2_b2") (pintype "passive"))
    )
    (net (code "141") (name "GND_+24V_BP") (class "Default")
      (node (ref "C32") (pin "1") (pinfunction "1_1") (pintype "passive"))
      (node (ref "J4") (pin "B32") (pinfunction "B32_B32") (pintype "passive"))
    )
    (net (code "142") (name "GND_D") (class "Default")
      (node (ref "C1") (pin "1") (pinfunction "1_1") (pintype "passive"))
      (node (ref "C2") (pin "1") (pinfunction "1_1") (pintype "passive"))
      (node (ref "C79") (pin "1") (pinfunction "1_1") (pintype "passive"))
      (node (ref "C80") (pin "1") (pinfunction "1_1") (pintype "passive"))
      (node (ref "C81") (pin "1") (pinfunction "1_1") (pintype "passive"))
      (node (ref "J1") (pin "a10") (pinfunction "a10_a10") (pintype "passive"))
      (node (ref "J1") (pin "a19") (pinfunction "a19_a19") (pintype "passive"))
      (node (ref "J1") (pin "b10") (pinfunction "b10_b10") (pintype "passive"))
      (node (ref "J1") (pin "b19") (pinfunction "b19_b19") (pintype "passive"))
      (node (ref "J10") (pin "a10") (pinfunction "a10_a10") (pintype "passive"))
      (node (ref "J10") (pin "a19") (pinfunction "a19_a19") (pintype "passive"))
      (node (ref "J10") (pin "b10") (pinfunction "b10_b10") (pintype "passive"))
      (node (ref "J10") (pin "b19") (pinfunction "b19_b19") (pintype "passive"))
      (node (ref "J3") (pin "10") (pinfunction "10_10") (pintype "passive"))
      (node (ref "J3") (pin "2") (pinfunction "2_2") (pintype "passive"))
      (node (ref "J3") (pin "4") (pinfunction "4_4") (pintype "passive"))
      (node (ref "J3") (pin "6") (pinfunction "6_6") (pintype "passive"))
      (node (ref "J3") (pin "8") (pinfunction "8_8") (pintype "passive"))
      (node (ref "J4") (pin "A1") (pinfunction "A1_A1") (pintype "passive"))
      (node (ref "J4") (pin "A10") (pinfunction "A10_A10") (pintype "passive"))
      (node (ref "J4") (pin "A13") (pinfunction "A13_A13") (pintype "passive"))
      (node (ref "J4") (pin "A18") (pinfunction "A18_A18") (pintype "passive"))
      (node (ref "J4") (pin "A23") (pinfunction "A23_A23") (pintype "passive"))
      (node (ref "J4") (pin "A28") (pinfunction "A28_A28") (pintype "passive"))
      (node (ref "J4") (pin "A30") (pinfunction "A30_A30") (pintype "passive"))
      (node (ref "J4") (pin "A4") (pinfunction "A4_A4") (pintype "passive"))
      (node (ref "J4") (pin "A7") (pinfunction "A7_A7") (pintype "passive"))
      (node (ref "J4") (pin "B1") (pinfunction "B1_B1") (pintype "passive"))
      (node (ref "J4") (pin "B10") (pinfunction "B10_B10") (pintype "passive"))
      (node (ref "J4") (pin "B13") (pinfunction "B13_B13") (pintype "passive"))
      (node (ref "J4") (pin "B18") (pinfunction "B18_B18") (pintype "passive"))
      (node (ref "J4") (pin "B23") (pinfunction "B23_B23") (pintype "passive"))
      (node (ref "J4") (pin "B28") (pinfunction "B28_B28") (pintype "passive"))
      (node (ref "J4") (pin "B30") (pinfunction "B30_B30") (pintype "passive"))
      (node (ref "J4") (pin "B4") (pinfunction "B4_B4") (pintype "passive"))
      (node (ref "J4") (pin "B7") (pinfunction "B7_B7") (pintype "passive"))
      (node (ref "J4") (pin "C1") (pinfunction "C1_C1") (pintype "passive"))
      (node (ref "J4") (pin "C10") (pinfunction "C10_C10") (pintype "passive"))
      (node (ref "J4") (pin "C13") (pinfunction "C13_C13") (pintype "passive"))
      (node (ref "J4") (pin "C18") (pinfunction "C18_C18") (pintype "passive"))
      (node (ref "J4") (pin "C23") (pinfunction "C23_C23") (pintype "passive"))
      (node (ref "J4") (pin "C28") (pinfunction "C28_C28") (pintype "passive"))
      (node (ref "J4") (pin "C30") (pinfunction "C30_C30") (pintype "passive"))
      (node (ref "J4") (pin "C4") (pinfunction "C4_C4") (pintype "passive"))
      (node (ref "J4") (pin "C7") (pinfunction "C7_C7") (pintype "passive"))
      (node (ref "J5") (pin "A1") (pinfunction "GND_A1") (pintype "passive"))
      (node (ref "J5") (pin "A12") (pinfunction "GND_A12") (pintype "passive"))
      (node (ref "J5") (pin "B1") (pinfunction "GND_B1") (pintype "passive"))
      (node (ref "J5") (pin "B12") (pinfunction "GND_B12") (pintype "passive"))
      (node (ref "J5") (pin "S1") (pinfunction "Shield_S1") (pintype "passive"))
      (node (ref "J5") (pin "S2") (pinfunction "Shield_S2") (pintype "passive"))
      (node (ref "J5") (pin "S3") (pinfunction "Shield_S3") (pintype "passive"))
      (node (ref "J5") (pin "S4") (pinfunction "Shield_S4") (pintype "passive"))
      (node (ref "R58") (pin "2") (pinfunction "2_2") (pintype "passive"))
      (node (ref "R59") (pin "2") (pinfunction "2_2") (pintype "passive"))
      (node (ref "U1") (pin "17") (pinfunction "GND_17") (pintype "passive"))
      (node (ref "U1") (pin "20") (pinfunction "GND_20") (pintype "passive"))
      (node (ref "U1") (pin "24") (pinfunction "AGND_24") (pintype "passive"))
      (node (ref "U1") (pin "26") (pinfunction "TEST_26") (pintype "passive"))
      (node (ref "U1") (pin "33") (pinfunction "EPAD_33") (pintype "passive"))
      (node (ref "U1") (pin "4") (pinfunction "GND_4") (pintype "passive"))
    )
    (net (code "143") (name "Net-(C1-Pad2)") (class "Default")
      (node (ref "C1") (pin "2") (pinfunction "2_2") (pintype "passive"))
      (node (ref "J5") (pin "A4") (pinfunction "VBUS_A4") (pintype "passive"))
      (node (ref "J5") (pin "A9") (pinfunction "VBUS_A9") (pintype "passive"))
      (node (ref "J5") (pin "B4") (pinfunction "VBUS_B4") (pintype "passive"))
      (node (ref "J5") (pin "B9") (pinfunction "VBUS_B9") (pintype "passive"))
      (node (ref "R7") (pin "1") (pinfunction "1_1") (pintype "passive"))
    )
    (net (code "144") (name "Net-(J5-CC1)") (class "Default")
      (node (ref "J5") (pin "A5") (pinfunction "CC1_A5") (pintype "passive"))
      (node (ref "R58") (pin "1") (pinfunction "1_1") (pintype "passive"))
    )
    (net (code "145") (name "Net-(J5-CC2)") (class "Default")
      (node (ref "J5") (pin "B5") (pinfunction "CC2_B5") (pintype "passive"))
      (node (ref "R59") (pin "1") (pinfunction "1_1") (pintype "passive"))
    )
    (net (code "146") (name "Net-(LD1-A)") (class "Default")
      (node (ref "LD1") (pin "2") (pinfunction "A_2") (pintype "passive"))
      (node (ref "R5") (pin "1") (pinfunction "1_1") (pintype "passive"))
    )
    (net (code "147") (name "Net-(LD2-A)") (class "Default")
      (node (ref "LD2") (pin "2") (pinfunction "A_2") (pintype "passive"))
      (node (ref "R6") (pin "1") (pinfunction "1_1") (pintype "passive"))
    )
    (net (code "148") (name "Net-(U1-3V3OUT)") (class "Default")
      (node (ref "C2") (pin "2") (pinfunction "2_2") (pintype "passive"))
      (node (ref "U1") (pin "16") (pinfunction "3V3OUT_16") (pintype "passive"))
    )
    (net (code "149") (name "unconnected-(J1-Pada1)") (class "Default")
      (node (ref "J1") (pin "a1") (pinfunction "a1_a1") (pintype "passive+no_connect"))
    )
    (net (code "150") (name "unconnected-(J1-Pada13)") (class "Default")
      (node (ref "J1") (pin "a13") (pinfunction "a13_a13") (pintype "passive+no_connect"))
    )
    (net (code "151") (name "unconnected-(J1-Pada14)") (class "Default")
      (node (ref "J1") (pin "a14") (pinfunction "a14_a14") (pintype "passive+no_connect"))
    )
    (net (code "152") (name "unconnected-(J1-Pada15)") (class "Default")
      (node (ref "J1") (pin "a15") (pinfunction "a15_a15") (pintype "passive+no_connect"))
    )
    (net (code "153") (name "unconnected-(J1-Pada16)") (class "Default")
      (node (ref "J1") (pin "a16") (pinfunction "a16_a16") (pintype "passive+no_connect"))
    )
    (net (code "154") (name "unconnected-(J1-Pada17)") (class "Default")
      (node (ref "J1") (pin "a17") (pinfunction "a17_a17") (pintype "passive+no_connect"))
    )
    (net (code "155") (name "unconnected-(J1-Pada18)") (class "Default")
      (node (ref "J1") (pin "a18") (pinfunction "a18_a18") (pintype "passive+no_connect"))
    )
    (net (code "156") (name "unconnected-(J1-Pada20)") (class "Default")
      (node (ref "J1") (pin "a20") (pinfunction "a20_a20") (pintype "passive+no_connect"))
    )
    (net (code "157") (name "unconnected-(J1-Pada21)") (class "Default")
      (node (ref "J1") (pin "a21") (pinfunction "a21_a21") (pintype "passive+no_connect"))
    )
    (net (code "158") (name "unconnected-(J1-Pada22)") (class "Default")
      (node (ref "J1") (pin "a22") (pinfunction "a22_a22") (pintype "passive+no_connect"))
    )
    (net (code "159") (name "unconnected-(J1-Pada23)") (class "Default")
      (node (ref "J1") (pin "a23") (pinfunction "a23_a23") (pintype "passive+no_connect"))
    )
    (net (code "160") (name "unconnected-(J1-Pada24)") (class "Default")
      (node (ref "J1") (pin "a24") (pinfunction "a24_a24") (pintype "passive+no_connect"))
    )
    (net (code "161") (name "unconnected-(J1-Pada25)") (class "Default")
      (node (ref "J1") (pin "a25") (pinfunction "a25_a25") (pintype "passive+no_connect"))
    )
    (net (code "162") (name "unconnected-(J1-Padb1)") (class "Default")
      (node (ref "J1") (pin "b1") (pinfunction "b1_b1") (pintype "passive+no_connect"))
    )
    (net (code "163") (name "unconnected-(J1-Padb14)") (class "Default")
      (node (ref "J1") (pin "b14") (pinfunction "b14_b14") (pintype "passive+no_connect"))
    )
    (net (code "164") (name "unconnected-(J1-Padb15)") (class "Default")
      (node (ref "J1") (pin "b15") (pinfunction "b15_b15") (pintype "passive+no_connect"))
    )
    (net (code "165") (name "unconnected-(J1-Padb16)") (class "Default")
      (node (ref "J1") (pin "b16") (pinfunction "b16_b16") (pintype "passive+no_connect"))
    )
    (net (code "166") (name "unconnected-(J1-Padb17)") (class "Default")
      (node (ref "J1") (pin "b17") (pinfunction "b17_b17") (pintype "passive+no_connect"))
    )
    (net (code "167") (name "unconnected-(J1-Padb18)") (class "Default")
      (node (ref "J1") (pin "b18") (pinfunction "b18_b18") (pintype "passive+no_connect"))
    )
    (net (code "168") (name "unconnected-(J1-Padb20)") (class "Default")
      (node (ref "J1") (pin "b20") (pinfunction "b20_b20") (pintype "passive+no_connect"))
    )
    (net (code "169") (name "unconnected-(J1-Padb24)") (class "Default")
      (node (ref "J1") (pin "b24") (pinfunction "b24_b24") (pintype "passive+no_connect"))
    )
    (net (code "170") (name "unconnected-(J2-Pada1)") (class "Default")
      (node (ref "J2") (pin "a1") (pinfunction "a1_a1") (pintype "passive+no_connect"))
    )
    (net (code "171") (name "unconnected-(J2-Pada5)") (class "Default")
      (node (ref "J2") (pin "a5") (pinfunction "a5_a5") (pintype "passive+no_connect"))
    )
    (net (code "172") (name "unconnected-(J2-Pada12)") (class "Default")
      (node (ref "J2") (pin "a12") (pinfunction "a12_a12") (pintype "passive+no_connect"))
    )
    (net (code "173") (name "unconnected-(J2-Pada15)") (class "Default")
      (node (ref "J2") (pin "a15") (pinfunction "a15_a15") (pintype "passive+no_connect"))
    )
    (net (code "174") (name "unconnected-(J2-Pada17)") (class "Default")
      (node (ref "J2") (pin "a17") (pinfunction "a17_a17") (pintype "passive+no_connect"))
    )
    (net (code "175") (name "unconnected-(J2-Padb1)") (class "Default")
      (node (ref "J2") (pin "b1") (pinfunction "b1_b1") (pintype "passive+no_connect"))
    )
    (net (code "176") (name "unconnected-(J2-Padb5)") (class "Default")
      (node (ref "J2") (pin "b5") (pinfunction "b5_b5") (pintype "passive+no_connect"))
    )
    (net (code "177") (name "unconnected-(J2-Padb12)") (class "Default")
      (node (ref "J2") (pin "b12") (pinfunction "b12_b12") (pintype "passive"))
    )
    (net (code "178") (name "unconnected-(J2-Padb14)") (class "Default")
      (node (ref "J2") (pin "b14") (pinfunction "b14_b14") (pintype "passive+no_connect"))
    )
    (net (code "179") (name "unconnected-(J2-Padb15)") (class "Default")
      (node (ref "J2") (pin "b15") (pinfunction "b15_b15") (pintype "passive+no_connect"))
    )
    (net (code "180") (name "unconnected-(J2-Padb17)") (class "Default")
      (node (ref "J2") (pin "b17") (pinfunction "b17_b17") (pintype "passive+no_connect"))
    )
    (net (code "181") (name "unconnected-(J2-Padb25)") (class "Default")
      (node (ref "J2") (pin "b25") (pinfunction "b25_b25") (pintype "passive+no_connect"))
    )
    (net (code "182") (name "unconnected-(J10-Pada1)") (class "Default")
      (node (ref "J10") (pin "a1") (pinfunction "a1_a1") (pintype "passive+no_connect"))
    )
    (net (code "183") (name "unconnected-(J10-Pada13)") (class "Default")
      (node (ref "J10") (pin "a13") (pinfunction "a13_a13") (pintype "passive+no_connect"))
    )
    (net (code "184") (name "unconnected-(J10-Pada14)") (class "Default")
      (node (ref "J10") (pin "a14") (pinfunction "a14_a14") (pintype "passive+no_connect"))
    )
    (net (code "185") (name "unconnected-(J10-Pada15)") (class "Default")
      (node (ref "J10") (pin "a15") (pinfunction "a15_a15") (pintype "passive+no_connect"))
    )
    (net (code "186") (name "unconnected-(J10-Pada16)") (class "Default")
      (node (ref "J10") (pin "a16") (pinfunction "a16_a16") (pintype "passive+no_connect"))
    )
    (net (code "187") (name "unconnected-(J10-Pada17)") (class "Default")
      (node (ref "J10") (pin "a17") (pinfunction "a17_a17") (pintype "passive+no_connect"))
    )
    (net (code "188") (name "unconnected-(J10-Pada18)") (class "Default")
      (node (ref "J10") (pin "a18") (pinfunction "a18_a18") (pintype "passive+no_connect"))
    )
    (net (code "189") (name "unconnected-(J10-Pada20)") (class "Default")
      (node (ref "J10") (pin "a20") (pinfunction "a20_a20") (pintype "passive+no_connect"))
    )
    (net (code "190") (name "unconnected-(J10-Pada21)") (class "Default")
      (node (ref "J10") (pin "a21") (pinfunction "a21_a21") (pintype "passive+no_connect"))
    )
    (net (code "191") (name "unconnected-(J10-Pada22)") (class "Default")
      (node (ref "J10") (pin "a22") (pinfunction "a22_a22") (pintype "passive+no_connect"))
    )
    (net (code "192") (name "unconnected-(J10-Pada23)") (class "Default")
      (node (ref "J10") (pin "a23") (pinfunction "a23_a23") (pintype "passive+no_connect"))
    )
    (net (code "193") (name "unconnected-(J10-Pada24)") (class "Default")
      (node (ref "J10") (pin "a24") (pinfunction "a24_a24") (pintype "passive+no_connect"))
    )
    (net (code "194") (name "unconnected-(J10-Pada25)") (class "Default")
      (node (ref "J10") (pin "a25") (pinfunction "a25_a25") (pintype "passive+no_connect"))
    )
    (net (code "195") (name "unconnected-(J10-Padb1)") (class "Default")
      (node (ref "J10") (pin "b1") (pinfunction "b1_b1") (pintype "passive+no_connect"))
    )
    (net (code "196") (name "unconnected-(J10-Padb14)") (class "Default")
      (node (ref "J10") (pin "b14") (pinfunction "b14_b14") (pintype "passive+no_connect"))
    )
    (net (code "197") (name "unconnected-(J10-Padb15)") (class "Default")
      (node (ref "J10") (pin "b15") (pinfunction "b15_b15") (pintype "passive+no_connect"))
    )
    (net (code "198") (name "unconnected-(J10-Padb16)") (class "Default")
      (node (ref "J10") (pin "b16") (pinfunction "b16_b16") (pintype "passive+no_connect"))
    )
    (net (code "199") (name "unconnected-(J10-Padb17)") (class "Default")
      (node (ref "J10") (pin "b17") (pinfunction "b17_b17") (pintype "passive+no_connect"))
    )
    (net (code "200") (name "unconnected-(J10-Padb18)") (class "Default")
      (node (ref "J10") (pin "b18") (pinfunction "b18_b18") (pintype "passive+no_connect"))
    )
    (net (code "201") (name "unconnected-(J10-Padb20)") (class "Default")
      (node (ref "J10") (pin "b20") (pinfunction "b20_b20") (pintype "passive+no_connect"))
    )
    (net (code "202") (name "unconnected-(J10-Padb24)") (class "Default")
      (node (ref "J10") (pin "b24") (pinfunction "b24_b24") (pintype "passive+no_connect"))
    )
    (net (code "203") (name "unconnected-(J11-Pada1)") (class "Default")
      (node (ref "J11") (pin "a1") (pinfunction "a1_a1") (pintype "passive+no_connect"))
    )
    (net (code "204") (name "unconnected-(J11-Pada5)") (class "Default")
      (node (ref "J11") (pin "a5") (pinfunction "a5_a5") (pintype "passive+no_connect"))
    )
    (net (code "205") (name "unconnected-(J11-Pada12)") (class "Default")
      (node (ref "J11") (pin "a12") (pinfunction "a12_a12") (pintype "passive+no_connect"))
    )
    (net (code "206") (name "unconnected-(J11-Pada15)") (class "Default")
      (node (ref "J11") (pin "a15") (pinfunction "a15_a15") (pintype "passive+no_connect"))
    )
    (net (code "207") (name "unconnected-(J11-Pada17)") (class "Default")
      (node (ref "J11") (pin "a17") (pinfunction "a17_a17") (pintype "passive+no_connect"))
    )
    (net (code "208") (name "unconnected-(J11-Padb1)") (class "Default")
      (node (ref "J11") (pin "b1") (pinfunction "b1_b1") (pintype "passive+no_connect"))
    )
    (net (code "209") (name "unconnected-(J11-Padb5)") (class "Default")
      (node (ref "J11") (pin "b5") (pinfunction "b5_b5") (pintype "passive+no_connect"))
    )
    (net (code "210") (name "unconnected-(J11-Padb12)") (class "Default")
      (node (ref "J11") (pin "b12") (pinfunction "b12_b12") (pintype "passive"))
    )
    (net (code "211") (name "unconnected-(J11-Padb14)") (class "Default")
      (node (ref "J11") (pin "b14") (pinfunction "b14_b14") (pintype "passive+no_connect"))
    )
    (net (code "212") (name "unconnected-(J11-Padb15)") (class "Default")
      (node (ref "J11") (pin "b15") (pinfunction "b15_b15") (pintype "passive+no_connect"))
    )
    (net (code "213") (name "unconnected-(J11-Padb17)") (class "Default")
      (node (ref "J11") (pin "b17") (pinfunction "b17_b17") (pintype "passive+no_connect"))
    )
    (net (code "214") (name "unconnected-(J11-Padb25)") (class "Default")
      (node (ref "J11") (pin "b25") (pinfunction "b25_b25") (pintype "passive+no_connect"))
    )
    (net (code "215") (name "unconnected-(U1-CBUS2-Pad10)") (class "Default")
      (node (ref "U1") (pin "10") (pinfunction "CBUS2_10") (pintype "passive+no_connect"))
    )
    (net (code "216") (name "unconnected-(U1-CBUS3-Pad11)") (class "Default")
      (node (ref "U1") (pin "11") (pinfunction "CBUS3_11") (pintype "passive+no_connect"))
    )
    (net (code "217") (name "unconnected-(U1-CBUS4-Pad9)") (class "Default")
      (node (ref "U1") (pin "9") (pinfunction "CBUS4_9") (pintype "passive+no_connect"))
    )
    (net (code "218") (name "unconnected-(U1-OSCI-Pad27)") (class "Default")
      (node (ref "U1") (pin "27") (pinfunction "OSCI_27") (pintype "passive+no_connect"))
    )
    (net (code "219") (name "unconnected-(U1-OSCO-Pad28)") (class "Default")
      (node (ref "U1") (pin "28") (pinfunction "OSCO_28") (pintype "passive+no_connect"))
    )
    (net (code "220") (name "unconnected-(U1-Pad5)") (class "Default")
      (node (ref "U1") (pin "5") (pintype "passive"))
    )
    (net (code "221") (name "unconnected-(U1-Pad12)") (class "Default")
      (node (ref "U1") (pin "12") (pintype "passive"))
    )
    (net (code "222") (name "unconnected-(U1-Pad13)") (class "Default")
      (node (ref "U1") (pin "13") (pintype "passive"))
    )
    (net (code "223") (name "unconnected-(U1-Pad23)") (class "Default")
      (node (ref "U1") (pin "23") (pintype "passive"))
    )
    (net (code "224") (name "unconnected-(U1-Pad25)") (class "Default")
      (node (ref "U1") (pin "25") (pintype "passive"))
    )
    (net (code "225") (name "unconnected-(U1-Pad29)") (class "Default")
      (node (ref "U1") (pin "29") (pintype "passive"))
    )
    (net (code "226") (name "unconnected-(U1-~{DCD}-Pad7)") (class "Default")
      (node (ref "U1") (pin "7") (pinfunction "~{DCD}_7") (pintype "passive+no_connect"))
    )
    (net (code "227") (name "unconnected-(U1-~{DSR}-Pad6)") (class "Default")
      (node (ref "U1") (pin "6") (pinfunction "~{DSR}_6") (pintype "passive+no_connect"))
    )
    (net (code "228") (name "unconnected-(U1-~{DTR}-Pad31)") (class "Default")
      (node (ref "U1") (pin "31") (pinfunction "~{DTR}_31") (pintype "passive+no_connect"))
    )
    (net (code "229") (name "unconnected-(U1-~{RESET}-Pad18)") (class "Default")
      (node (ref "U1") (pin "18") (pinfunction "~{RESET}_18") (pintype "passive+no_connect"))
    )
    (net (code "230") (name "unconnected-(U1-~{RI}-Pad3)") (class "Default")
      (node (ref "U1") (pin "3") (pinfunction "~{RI}_3") (pintype "passive+no_connect"))
    )
  )
)
